# transimpedance_amplifier.net
KiCad netlist of a schematic drawn in EAGLE
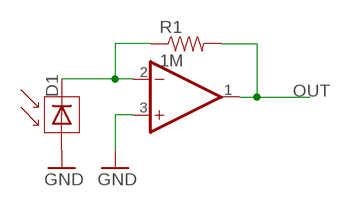
[diagram p0: schematic, sheet 1]

(export (version "E")
  (design (tool "Eeschema 10.0.6"))
  (components
    (comp (ref "D1")
      (value "SOLAR-IXYS-")
      (footprint "eagle-import:SOLARBIT-12X1")
      (libsource (lib "eagle-import") (part "SOLAR-IXYS-"))
    )
    (comp (ref "IC1")
      (value "MCP6022")
      (footprint "eagle-import:SOIC8_150MIL")
      (libsource (lib "eagle-import") (part "MCP6022"))
    )
    (comp (ref "R1")
      (value "1M")
      (footprint "eagle-import:0402-RES")
      (libsource (lib "eagle-import") (part "RESISTOR0402-RES"))
    )
  )
  (nets
    (net (code "1") (name "/OUT") (class "Default")
      (node (ref "IC1") (pin "1") (pinfunction "OUT_1") (pintype "output"))
      (node (ref "R1") (pin "2") (pinfunction "2_2") (pintype "passive"))
    )
    (net (code "2") (name "GND") (class "Default")
      (node (ref "D1") (pin "+") (pinfunction "A_+") (pintype "passive"))
      (node (ref "IC1") (pin "3") (pinfunction "+IN_3") (pintype "input"))
    )
    (net (code "3") (name "Net-(D1-C)") (class "Default")
      (node (ref "D1") (pin "-") (pinfunction "C_-") (pintype "passive"))
      (node (ref "IC1") (pin "2") (pinfunction "-IN_2") (pintype "input"))
      (node (ref "R1") (pin "1") (pinfunction "1_1") (pintype "passive"))
    )
  )
)
